# CR20-0611.net
KiCad netlist of a schematic drawn in Altium Designer
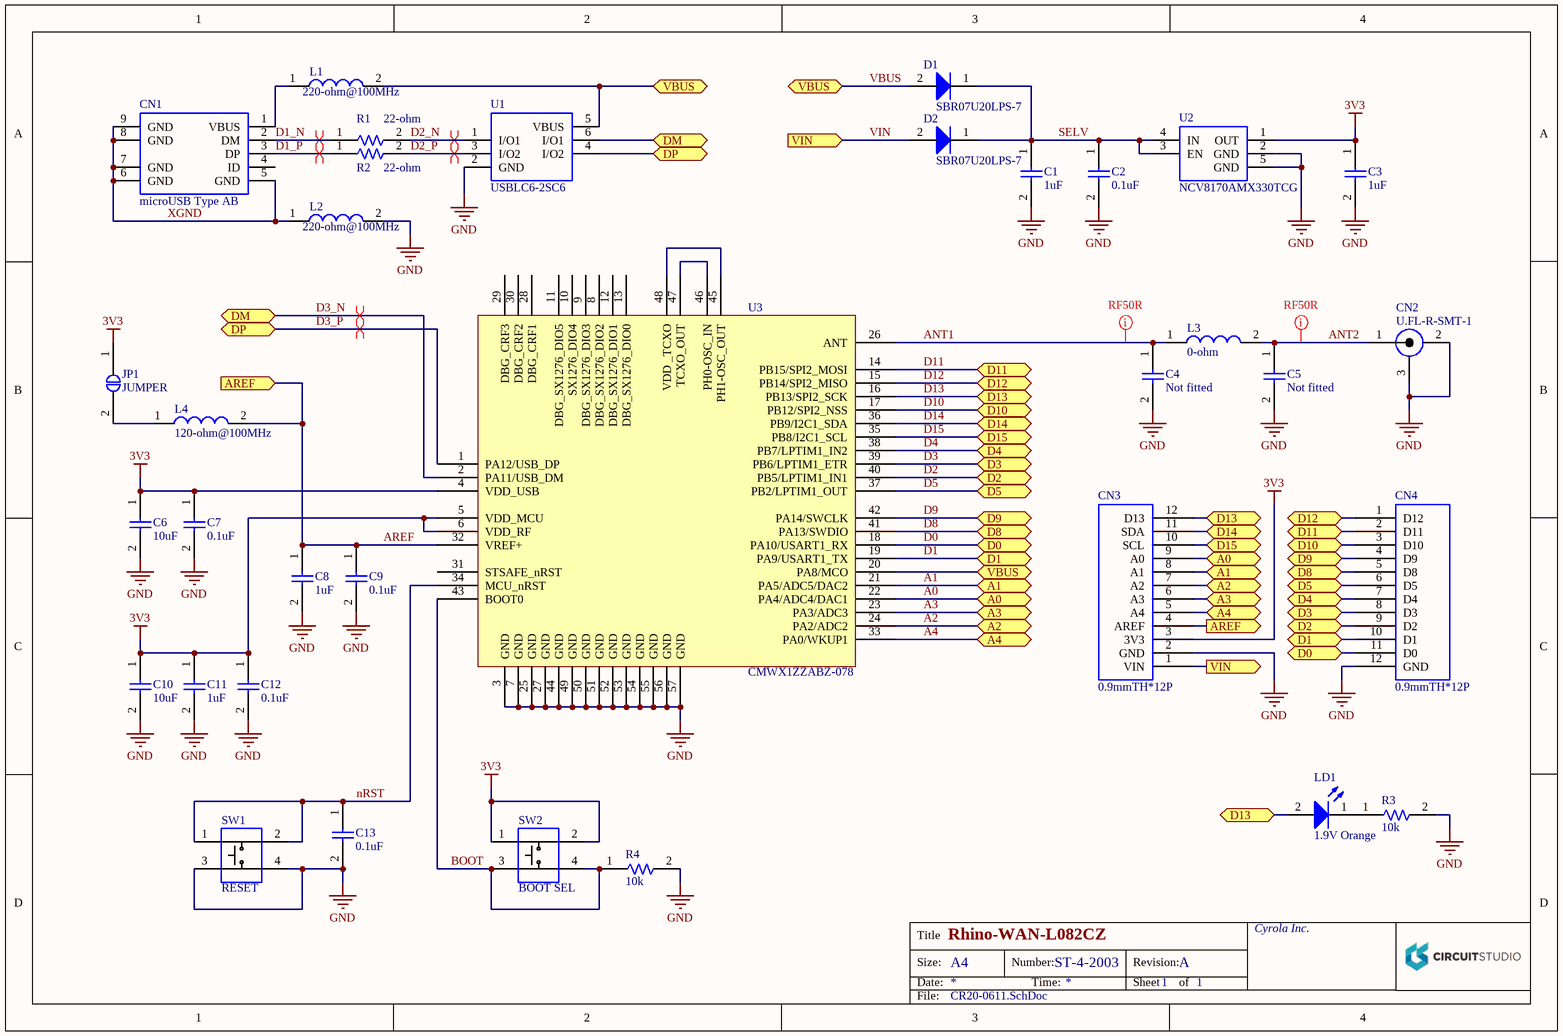
[diagram p0: CR20-0611.SchDoc]

(export (version "E")
  (design (tool "Eeschema 10.0.6"))
  (components
    (comp (ref "C1")
      (value "1uF")
      (footprint "CAPC1005X06N")
      (description "1005 1uF 10% X5R 25V")
      (libsource (lib "GRM15") (part "GRM155R61E105KA12D"))
    )
    (comp (ref "C2")
      (value "0.1uF")
      (footprint "CAPC1005X06N")
      (description "1005 0.1uF 10% X7R 50V")
      (libsource (lib "GRM15") (part "GRM155R71H104KE14J"))
    )
    (comp (ref "C3")
      (value "1uF")
      (footprint "CAPC1005X06N")
      (description "1005 1uF 10% X5R 25V")
      (libsource (lib "GRM15") (part "GRM155R61E105KA12D"))
    )
    (comp (ref "C4")
      (value "Not fitted")
      (footprint "CAPC0603X03N")
      (description "0603")
      (libsource (lib "GRM033") (part "GRM0335C1H220FA01D"))
    )
    (comp (ref "C5")
      (value "Not fitted")
      (footprint "CAPC0603X03N")
      (description "0603")
      (libsource (lib "GRM033") (part "GRM0335C1H220FA01D"))
    )
    (comp (ref "C6")
      (value "10uF")
      (footprint "CAPC1005X06N")
      (description "1005 10uF 20% X5R 6.3V")
      (libsource (lib "GRM15") (part "GRM155R60J106ME15D"))
    )
    (comp (ref "C7")
      (value "0.1uF")
      (footprint "CAPC1005X06N")
      (description "1005 0.1uF 10% X7R 50V")
      (libsource (lib "GRM15") (part "GRM155R71H104KE14J"))
    )
    (comp (ref "C8")
      (value "1uF")
      (footprint "CAPC1005X06N")
      (description "1005 1uF 10% X5R 25V")
      (libsource (lib "GRM15") (part "GRM155R61E105KA12D"))
    )
    (comp (ref "C9")
      (value "0.1uF")
      (footprint "CAPC1005X06N")
      (description "1005 0.1uF 10% X7R 50V")
      (libsource (lib "GRM15") (part "GRM155R71H104KE14J"))
    )
    (comp (ref "C10")
      (value "10uF")
      (footprint "CAPC1005X06N")
      (description "1005 10uF 20% X5R 6.3V")
      (libsource (lib "GRM15") (part "GRM155R60J106ME15D"))
    )
    (comp (ref "C11")
      (value "1uF")
      (footprint "CAPC1005X06N")
      (description "1005 1uF 10% X5R 25V")
      (libsource (lib "GRM15") (part "GRM155R61E105KA12D"))
    )
    (comp (ref "C12")
      (value "0.1uF")
      (footprint "CAPC1005X06N")
      (description "1005 0.1uF 10% X7R 50V")
      (libsource (lib "GRM15") (part "GRM155R71H104KE14J"))
    )
    (comp (ref "C13")
      (value "0.1uF")
      (footprint "CAPC1005X06N")
      (description "1005 0.1uF 10% X7R 50V")
      (libsource (lib "GRM15") (part "GRM155R71H104KE14J"))
    )
    (comp (ref "CN1")
      (value "microUSB Type AB")
      (footprint "1981584-1")
      (description "Micro USB Receptacle Type AB")
      (libsource (lib "1981584-1") (part "1981584-1"))
    )
    (comp (ref "CN2")
      (value "U.FL-R-SMT-1")
      (footprint "U_FL-R-SMT-1")
      (description "SMT ultra-small coaxial connector")
      (libsource (lib "U_FL-R-SMT-1") (part "U_FL-R-SMT-1"))
    )
    (comp (ref "CN3")
      (value "0.9mmTH*12P")
      (footprint "61301211121")
      (description "WR-PHD Pin Header 12pin")
      (libsource (lib "61301211121") (part "RHINO_WAN_L"))
    )
    (comp (ref "CN4")
      (value "0.9mmTH*12P")
      (footprint "61301211121")
      (description "WR-PHD Pin Header 12pin")
      (libsource (lib "61301211121") (part "RHINO_WAN_R"))
    )
    (comp (ref "D1")
      (value "SBR07U20LPS-7")
      (footprint "SBR07U20LPS-7")
      (description "Super Barrier Rectifier")
      (libsource (lib "SBR07U20LPS-7") (part "SBR07U20LPS-7"))
    )
    (comp (ref "D2")
      (value "SBR07U20LPS-7")
      (footprint "SBR07U20LPS-7")
      (description "Super Barrier Rectifier")
      (libsource (lib "SBR07U20LPS-7") (part "SBR07U20LPS-7"))
    )
    (comp (ref "JP1")
      (value "JUMPER")
      (footprint "Solder Jumper")
      (description "Jumper Pad")
      (libsource (lib "SOLDER_JUMPER") (part "SOLDER_JUMPER"))
    )
    (comp (ref "L1")
      (value "220-ohm@100MHz")
      (footprint "INDC1005X06N")
      (description "Chip Ferrite Bead 1005")
      (libsource (lib "BLM15") (part "BLM15PX221SN1D"))
    )
    (comp (ref "L2")
      (value "220-ohm@100MHz")
      (footprint "INDC1005X06N")
      (description "Chip Ferrite Bead 1005")
      (libsource (lib "BLM15") (part "BLM15PX221SN1D"))
    )
    (comp (ref "L3")
      (value "0-ohm")
      (footprint "INDC0603X04N")
      (description "RK73Z1HTTC")
      (libsource (lib "LQP03HQ10NH02D") (part "LQP03HQ10NH02D"))
    )
    (comp (ref "L4")
      (value "120-ohm@100MHz")
      (footprint "INDC1005X06N")
      (description "Chip Ferrite Bead 1005")
      (libsource (lib "BLM15") (part "BLM15AG121SN1D"))
    )
    (comp (ref "LD1")
      (value "1.9V Orange")
      (footprint "DIOM1006X02N")
      (description "Ultra-small LED Orange")
      (libsource (lib "SML-P11") (part "SML-P11DTT86R"))
    )
    (comp (ref "R1")
      (value "22-ohm")
      (footprint "RESC1005X04N")
      (description "1005 22-ohm 1/10W")
      (libsource (lib "RK73B1E") (part "RK73B1ETTP220J"))
    )
    (comp (ref "R2")
      (value "22-ohm")
      (footprint "RESC1005X04N")
      (description "1005 22-ohm 1/10W")
      (libsource (lib "RK73B1E") (part "RK73B1ETTP220J"))
    )
    (comp (ref "R3")
      (value "10k")
      (footprint "RESC1005X04N")
      (description "1005 10k 1/10W")
      (libsource (lib "RK73B1E") (part "RK73B1ETTP103J"))
    )
    (comp (ref "R4")
      (value "10k")
      (footprint "RESC1005X04N")
      (description "1005 10k 1/10W")
      (libsource (lib "RK73B1E") (part "RK73B1ETTP103J"))
    )
    (comp (ref "SW1")
      (value "RESET")
      (footprint "SKRPABE010")
      (description "SPST Switch N/O 1.57N")
      (libsource (lib "SKRPABE010") (part "SKRPABE010"))
    )
    (comp (ref "SW2")
      (value "BOOT SEL")
      (footprint "SKRPABE010")
      (description "SPST Switch N/O 1.57N")
      (libsource (lib "SKRPABE010") (part "SKRPABE010"))
    )
    (comp (ref "U1")
      (value "USBLC6-2SC6")
      (footprint "USBLC6-2SC6")
      (description "ESD protection")
      (libsource (lib "USBLC6-2SC6") (part "USBLC6-2SC6"))
    )
    (comp (ref "U2")
      (value "NCV8170AMX330TCG")
      (footprint "NCV8170AMX330TCG")
      (description "Ultra-Low Noise LDO Regulator")
      (libsource (lib "NCV8170AMX330TCG") (part "NCV8170AMX330TCG"))
    )
    (comp (ref "U3")
      (value "CMWX1ZZABZ-078")
      (footprint "CMWX1ZZABZ-078")
      (description "Sub-G Module")
      (libsource (lib "CMWX1ZZABZ-078") (part "CMWX1ZZABZ-078"))
    )
  )
  (nets
    (net (code "1") (name "/A0") (class "Default")
      (node (ref "CN3") (pin "9") (pinfunction "A0_9") (pintype "passive"))
      (node (ref "U3") (pin "22") (pinfunction "PA4/ADC4/DAC1_22") (pintype "passive"))
    )
    (net (code "2") (name "/A1") (class "Default")
      (node (ref "CN3") (pin "8") (pinfunction "A1_8") (pintype "passive"))
      (node (ref "U3") (pin "21") (pinfunction "PA5/ADC5/DAC2_21") (pintype "passive"))
    )
    (net (code "3") (name "/A2") (class "Default")
      (node (ref "CN3") (pin "7") (pinfunction "A2_7") (pintype "passive"))
      (node (ref "U3") (pin "24") (pinfunction "PA2/ADC2_24") (pintype "passive"))
    )
    (net (code "4") (name "/A3") (class "Default")
      (node (ref "CN3") (pin "6") (pinfunction "A3_6") (pintype "passive"))
      (node (ref "U3") (pin "23") (pinfunction "PA3/ADC3_23") (pintype "passive"))
    )
    (net (code "5") (name "/A4") (class "Default")
      (node (ref "CN3") (pin "5") (pinfunction "A4_5") (pintype "passive"))
      (node (ref "U3") (pin "33") (pinfunction "PA0/WKUP1_33") (pintype "passive"))
    )
    (net (code "6") (name "/ANT1") (class "Default")
      (node (ref "C4") (pin "1") (pinfunction "1_1") (pintype "passive"))
      (node (ref "L3") (pin "1") (pinfunction "1_1") (pintype "passive"))
      (node (ref "U3") (pin "26") (pinfunction "ANT_26") (pintype "passive"))
    )
    (net (code "7") (name "/ANT2") (class "Default")
      (node (ref "C5") (pin "1") (pinfunction "1_1") (pintype "passive"))
      (node (ref "CN2") (pin "1") (pinfunction "SIG_1") (pintype "passive"))
      (node (ref "L3") (pin "2") (pinfunction "2_2") (pintype "passive"))
    )
    (net (code "8") (name "/AREF") (class "Default")
      (node (ref "C8") (pin "1") (pinfunction "1_1") (pintype "passive"))
      (node (ref "C9") (pin "1") (pinfunction "1_1") (pintype "passive"))
      (node (ref "CN3") (pin "4") (pinfunction "AREF_4") (pintype "passive"))
      (node (ref "L4") (pin "2") (pinfunction "2_2") (pintype "passive"))
      (node (ref "U3") (pin "32") (pinfunction "VREF+_32") (pintype "passive"))
    )
    (net (code "9") (name "/BOOT") (class "Default")
      (node (ref "R4") (pin "1") (pinfunction "1_1") (pintype "passive"))
      (node (ref "SW2") (pin "3") (pinfunction "3_3") (pintype "passive"))
      (node (ref "SW2") (pin "4") (pinfunction "4_4") (pintype "passive"))
      (node (ref "U3") (pin "43") (pinfunction "BOOT0_43") (pintype "passive"))
    )
    (net (code "10") (name "/D0") (class "Default")
      (node (ref "CN4") (pin "11") (pinfunction "D0_11") (pintype "passive"))
      (node (ref "U3") (pin "18") (pinfunction "PA10/USART1_RX_18") (pintype "passive"))
    )
    (net (code "11") (name "/D1") (class "Default")
      (node (ref "CN4") (pin "10") (pinfunction "D1_10") (pintype "passive"))
      (node (ref "U3") (pin "19") (pinfunction "PA9/USART1_TX_19") (pintype "passive"))
    )
    (net (code "12") (name "/D1_N") (class "Default")
      (node (ref "CN1") (pin "2") (pinfunction "DM_2") (pintype "passive"))
      (node (ref "R1") (pin "1") (pinfunction "1_1") (pintype "passive"))
    )
    (net (code "13") (name "/D1_P") (class "Default")
      (node (ref "CN1") (pin "3") (pinfunction "DP_3") (pintype "passive"))
      (node (ref "R2") (pin "1") (pinfunction "1_1") (pintype "passive"))
    )
    (net (code "14") (name "/D2") (class "Default")
      (node (ref "CN4") (pin "9") (pinfunction "D2_9") (pintype "passive"))
      (node (ref "U3") (pin "40") (pinfunction "PB5/LPTIM1_IN1_40") (pintype "passive"))
    )
    (net (code "15") (name "/D2_N") (class "Default")
      (node (ref "R1") (pin "2") (pinfunction "2_2") (pintype "passive"))
      (node (ref "U1") (pin "1") (pinfunction "I/O1_1") (pintype "passive"))
    )
    (net (code "16") (name "/D2_P") (class "Default")
      (node (ref "R2") (pin "2") (pinfunction "2_2") (pintype "passive"))
      (node (ref "U1") (pin "3") (pinfunction "I/O2_3") (pintype "passive"))
    )
    (net (code "17") (name "/D3") (class "Default")
      (node (ref "CN4") (pin "8") (pinfunction "D3_8") (pintype "passive"))
      (node (ref "U3") (pin "39") (pinfunction "PB6/LPTIM1_ETR_39") (pintype "passive"))
    )
    (net (code "18") (name "/D3_N") (class "Default")
      (node (ref "U1") (pin "6") (pinfunction "I/O1_6") (pintype "passive"))
      (node (ref "U3") (pin "2") (pinfunction "PA11/USB_DM_2") (pintype "passive"))
    )
    (net (code "19") (name "/D3_P") (class "Default")
      (node (ref "U1") (pin "4") (pinfunction "I/O2_4") (pintype "passive"))
      (node (ref "U3") (pin "1") (pinfunction "PA12/USB_DP_1") (pintype "passive"))
    )
    (net (code "20") (name "/D4") (class "Default")
      (node (ref "CN4") (pin "7") (pinfunction "D4_7") (pintype "passive"))
      (node (ref "U3") (pin "38") (pinfunction "PB7/LPTIM1_IN2_38") (pintype "passive"))
    )
    (net (code "21") (name "/D5") (class "Default")
      (node (ref "CN4") (pin "6") (pinfunction "D5_6") (pintype "passive"))
      (node (ref "U3") (pin "37") (pinfunction "PB2/LPTIM1_OUT_37") (pintype "passive"))
    )
    (net (code "22") (name "/D8") (class "Default")
      (node (ref "CN4") (pin "5") (pinfunction "D8_5") (pintype "passive"))
      (node (ref "U3") (pin "41") (pinfunction "PA13/SWDIO_41") (pintype "passive"))
    )
    (net (code "23") (name "/D9") (class "Default")
      (node (ref "CN4") (pin "4") (pinfunction "D9_4") (pintype "passive"))
      (node (ref "U3") (pin "42") (pinfunction "PA14/SWCLK_42") (pintype "passive"))
    )
    (net (code "24") (name "/D10") (class "Default")
      (node (ref "CN4") (pin "3") (pinfunction "D10_3") (pintype "passive"))
      (node (ref "U3") (pin "17") (pinfunction "PB12/SPI2_NSS_17") (pintype "passive"))
    )
    (net (code "25") (name "/D11") (class "Default")
      (node (ref "CN4") (pin "2") (pinfunction "D11_2") (pintype "passive"))
      (node (ref "U3") (pin "14") (pinfunction "PB15/SPI2_MOSI_14") (pintype "passive"))
    )
    (net (code "26") (name "/D12") (class "Default")
      (node (ref "CN4") (pin "1") (pinfunction "D12_1") (pintype "passive"))
      (node (ref "U3") (pin "15") (pinfunction "PB14/SPI2_MISO_15") (pintype "passive"))
    )
    (net (code "27") (name "/D13") (class "Default")
      (node (ref "CN3") (pin "12") (pinfunction "D13_12") (pintype "passive"))
      (node (ref "LD1") (pin "2") (pinfunction "2_2") (pintype "passive"))
      (node (ref "U3") (pin "16") (pinfunction "PB13/SPI2_SCK_16") (pintype "passive"))
    )
    (net (code "28") (name "/D14") (class "Default")
      (node (ref "CN3") (pin "11") (pinfunction "SDA_11") (pintype "passive"))
      (node (ref "U3") (pin "36") (pinfunction "PB9/I2C1_SDA_36") (pintype "passive"))
    )
    (net (code "29") (name "/D15") (class "Default")
      (node (ref "CN3") (pin "10") (pinfunction "SCL_10") (pintype "passive"))
      (node (ref "U3") (pin "35") (pinfunction "PB8/I2C1_SCL_35") (pintype "passive"))
    )
    (net (code "30") (name "/SELV") (class "Default")
      (node (ref "C1") (pin "1") (pinfunction "1_1") (pintype "passive"))
      (node (ref "C2") (pin "1") (pinfunction "1_1") (pintype "passive"))
      (node (ref "D1") (pin "1") (pinfunction "1_1") (pintype "passive"))
      (node (ref "D2") (pin "1") (pinfunction "1_1") (pintype "passive"))
      (node (ref "U2") (pin "3") (pinfunction "EN_3") (pintype "passive"))
      (node (ref "U2") (pin "4") (pinfunction "IN_4") (pintype "passive"))
    )
    (net (code "31") (name "/VBUS") (class "Default")
      (node (ref "D1") (pin "2") (pinfunction "2_2") (pintype "passive"))
      (node (ref "L1") (pin "2") (pinfunction "2_2") (pintype "passive"))
      (node (ref "U1") (pin "5") (pinfunction "VBUS_5") (pintype "passive"))
      (node (ref "U3") (pin "20") (pinfunction "PA8/MCO_20") (pintype "passive"))
    )
    (net (code "32") (name "/VIN") (class "Default")
      (node (ref "CN3") (pin "1") (pinfunction "VIN_1") (pintype "passive"))
      (node (ref "D2") (pin "2") (pinfunction "2_2") (pintype "passive"))
    )
    (net (code "33") (name "/XGND") (class "Default")
      (node (ref "CN1") (pin "5") (pinfunction "GND_5") (pintype "passive"))
      (node (ref "CN1") (pin "6") (pinfunction "GND_6") (pintype "passive"))
      (node (ref "CN1") (pin "7") (pinfunction "GND_7") (pintype "passive"))
      (node (ref "CN1") (pin "8") (pinfunction "GND_8") (pintype "passive"))
      (node (ref "CN1") (pin "9") (pinfunction "GND_9") (pintype "passive"))
      (node (ref "L2") (pin "1") (pinfunction "1_1") (pintype "passive"))
    )
    (net (code "34") (name "/nRST") (class "Default")
      (node (ref "C13") (pin "1") (pinfunction "1_1") (pintype "passive"))
      (node (ref "SW1") (pin "1") (pinfunction "1_1") (pintype "passive"))
      (node (ref "SW1") (pin "2") (pinfunction "2_2") (pintype "passive"))
      (node (ref "U3") (pin "34") (pinfunction "MCU_nRST_34") (pintype "passive"))
    )
    (net (code "35") (name "3V3") (class "Default")
      (node (ref "C10") (pin "1") (pinfunction "1_1") (pintype "passive"))
      (node (ref "C11") (pin "1") (pinfunction "1_1") (pintype "passive"))
      (node (ref "C12") (pin "1") (pinfunction "1_1") (pintype "passive"))
      (node (ref "C3") (pin "1") (pinfunction "1_1") (pintype "passive"))
      (node (ref "C6") (pin "1") (pinfunction "1_1") (pintype "passive"))
      (node (ref "C7") (pin "1") (pinfunction "1_1") (pintype "passive"))
      (node (ref "CN3") (pin "3") (pinfunction "3V3_3") (pintype "passive"))
      (node (ref "JP1") (pin "1") (pinfunction "1_1") (pintype "passive"))
      (node (ref "SW2") (pin "1") (pinfunction "1_1") (pintype "passive"))
      (node (ref "SW2") (pin "2") (pinfunction "2_2") (pintype "passive"))
      (node (ref "U2") (pin "1") (pinfunction "OUT_1") (pintype "passive"))
      (node (ref "U3") (pin "4") (pinfunction "VDD_USB_4") (pintype "passive"))
      (node (ref "U3") (pin "5") (pinfunction "VDD_MCU_5") (pintype "passive"))
      (node (ref "U3") (pin "6") (pinfunction "VDD_RF_6") (pintype "passive"))
    )
    (net (code "36") (name "GND") (class "Default")
      (node (ref "C1") (pin "2") (pinfunction "2_2") (pintype "passive"))
      (node (ref "C10") (pin "2") (pinfunction "2_2") (pintype "passive"))
      (node (ref "C11") (pin "2") (pinfunction "2_2") (pintype "passive"))
      (node (ref "C12") (pin "2") (pinfunction "2_2") (pintype "passive"))
      (node (ref "C13") (pin "2") (pinfunction "2_2") (pintype "passive"))
      (node (ref "C2") (pin "2") (pinfunction "2_2") (pintype "passive"))
      (node (ref "C3") (pin "2") (pinfunction "2_2") (pintype "passive"))
      (node (ref "C4") (pin "2") (pinfunction "2_2") (pintype "passive"))
      (node (ref "C5") (pin "2") (pinfunction "2_2") (pintype "passive"))
      (node (ref "C6") (pin "2") (pinfunction "2_2") (pintype "passive"))
      (node (ref "C7") (pin "2") (pinfunction "2_2") (pintype "passive"))
      (node (ref "C8") (pin "2") (pinfunction "2_2") (pintype "passive"))
      (node (ref "C9") (pin "2") (pinfunction "2_2") (pintype "passive"))
      (node (ref "CN2") (pin "2") (pinfunction "GND_2") (pintype "passive"))
      (node (ref "CN2") (pin "3") (pinfunction "GND_3") (pintype "passive"))
      (node (ref "CN3") (pin "2") (pinfunction "GND_2") (pintype "passive"))
      (node (ref "CN4") (pin "12") (pinfunction "GND_12") (pintype "passive"))
      (node (ref "L2") (pin "2") (pinfunction "2_2") (pintype "passive"))
      (node (ref "R3") (pin "2") (pinfunction "2_2") (pintype "passive"))
      (node (ref "R4") (pin "2") (pinfunction "2_2") (pintype "passive"))
      (node (ref "SW1") (pin "3") (pinfunction "3_3") (pintype "passive"))
      (node (ref "SW1") (pin "4") (pinfunction "4_4") (pintype "passive"))
      (node (ref "U1") (pin "2") (pinfunction "GND_2") (pintype "passive"))
      (node (ref "U2") (pin "2") (pinfunction "GND_2") (pintype "passive"))
      (node (ref "U2") (pin "5") (pinfunction "GND_5") (pintype "passive"))
      (node (ref "U3") (pin "25") (pinfunction "GND_25") (pintype "passive"))
      (node (ref "U3") (pin "27") (pinfunction "GND_27") (pintype "passive"))
      (node (ref "U3") (pin "3") (pinfunction "GND_3") (pintype "passive"))
      (node (ref "U3") (pin "44") (pinfunction "GND_44") (pintype "passive"))
      (node (ref "U3") (pin "49") (pinfunction "GND_49") (pintype "passive"))
      (node (ref "U3") (pin "50") (pinfunction "GND_50") (pintype "passive"))
      (node (ref "U3") (pin "51") (pinfunction "GND_51") (pintype "passive"))
      (node (ref "U3") (pin "52") (pinfunction "GND_52") (pintype "passive"))
      (node (ref "U3") (pin "53") (pinfunction "GND_53") (pintype "passive"))
      (node (ref "U3") (pin "54") (pinfunction "GND_54") (pintype "passive"))
      (node (ref "U3") (pin "55") (pinfunction "GND_55") (pintype "passive"))
      (node (ref "U3") (pin "56") (pinfunction "GND_56") (pintype "passive"))
      (node (ref "U3") (pin "57") (pinfunction "GND_57") (pintype "passive"))
      (node (ref "U3") (pin "7") (pinfunction "GND_7") (pintype "passive"))
    )
    (net (code "37") (name "Net-(CN1-VBUS)") (class "Default")
      (node (ref "CN1") (pin "1") (pinfunction "VBUS_1") (pintype "passive"))
      (node (ref "L1") (pin "1") (pinfunction "1_1") (pintype "passive"))
    )
    (net (code "38") (name "Net-(JP1-Pad2)") (class "Default")
      (node (ref "JP1") (pin "2") (pinfunction "2_2") (pintype "passive"))
      (node (ref "L4") (pin "1") (pinfunction "1_1") (pintype "passive"))
    )
    (net (code "39") (name "Net-(LD1-Pad1)") (class "Default")
      (node (ref "LD1") (pin "1") (pinfunction "1_1") (pintype "passive"))
      (node (ref "R3") (pin "1") (pinfunction "1_1") (pintype "passive"))
    )
    (net (code "40") (name "Net-(U3-PH0-OSC_IN)") (class "Default")
      (node (ref "U3") (pin "46") (pinfunction "PH0-OSC_IN_46") (pintype "passive"))
      (node (ref "U3") (pin "47") (pinfunction "TCXO_OUT_47") (pintype "passive"))
    )
    (net (code "41") (name "Net-(U3-PH1-OSC_OUT)") (class "Default")
      (node (ref "U3") (pin "45") (pinfunction "PH1-OSC_OUT_45") (pintype "passive"))
      (node (ref "U3") (pin "48") (pinfunction "VDD__TCXO_48") (pintype "passive"))
    )
    (net (code "42") (name "unconnected-(CN1-ID-Pad4)") (class "Default")
      (node (ref "CN1") (pin "4") (pinfunction "ID_4") (pintype "passive"))
    )
    (net (code "43") (name "unconnected-(U3-DBG_CRF1-Pad28)") (class "Default")
      (node (ref "U3") (pin "28") (pinfunction "DBG_CRF1_28") (pintype "passive"))
    )
    (net (code "44") (name "unconnected-(U3-DBG_CRF2-Pad30)") (class "Default")
      (node (ref "U3") (pin "30") (pinfunction "DBG_CRF2_30") (pintype "passive"))
    )
    (net (code "45") (name "unconnected-(U3-DBG_CRF3-Pad29)") (class "Default")
      (node (ref "U3") (pin "29") (pinfunction "DBG_CRF3_29") (pintype "passive"))
    )
    (net (code "46") (name "unconnected-(U3-DBG_SX1276_DIO0-Pad13)") (class "Default")
      (node (ref "U3") (pin "13") (pinfunction "DBG_SX1276_DIO0_13") (pintype "passive"))
    )
    (net (code "47") (name "unconnected-(U3-DBG_SX1276_DIO1-Pad12)") (class "Default")
      (node (ref "U3") (pin "12") (pinfunction "DBG_SX1276_DIO1_12") (pintype "passive"))
    )
    (net (code "48") (name "unconnected-(U3-DBG_SX1276_DIO2-Pad8)") (class "Default")
      (node (ref "U3") (pin "8") (pinfunction "DBG_SX1276_DIO2_8") (pintype "passive"))
    )
    (net (code "49") (name "unconnected-(U3-DBG_SX1276_DIO3-Pad9)") (class "Default")
      (node (ref "U3") (pin "9") (pinfunction "DBG_SX1276_DIO3_9") (pintype "passive"))
    )
    (net (code "50") (name "unconnected-(U3-DBG_SX1276_DIO5-Pad11)") (class "Default")
      (node (ref "U3") (pin "11") (pinfunction "DBG_SX1276_DIO5_11") (pintype "passive"))
    )
    (net (code "51") (name "unconnected-(U3-STSAFE_nRST-Pad31)") (class "Default")
      (node (ref "U3") (pin "31") (pinfunction "STSAFE_nRST_31") (pintype "passive"))
    )
    (net (code "52") (name "unconnected-(U3-SX1276_DIO4-Pad10)") (class "Default")
      (node (ref "U3") (pin "10") (pinfunction "SX1276_DIO4_10") (pintype "passive"))
    )
  )
)
